# untitled.net
KiCad netlist of a schematic drawn in EAGLE
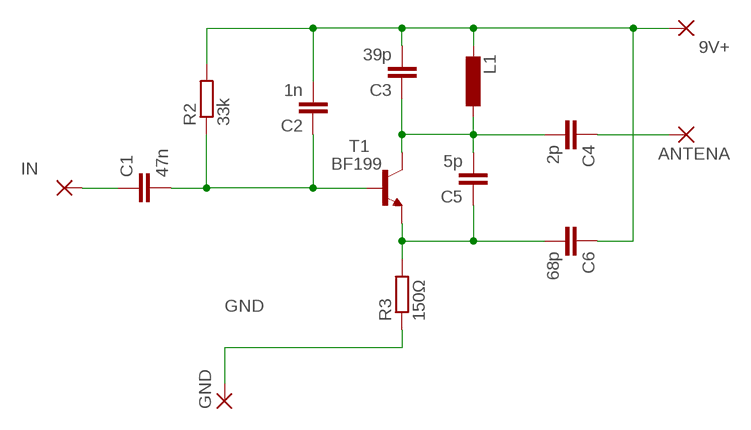
[diagram p0: schematic, sheet 1]

(export (version "E")
  (design (tool "Eeschema 10.0.6"))
  (components
    (comp (ref "9V+")
      (value "3,81/1,4")
      (footprint "eagle-import:3,81_1,4")
      (libsource (lib "eagle-import") (part "3,81/1,4"))
    )
    (comp (ref "ANTENA")
      (value "3,81/1,4")
      (footprint "eagle-import:3,81_1,4")
      (libsource (lib "eagle-import") (part "3,81/1,4"))
    )
    (comp (ref "C1")
      (value "47n")
      (footprint "eagle-import:C025-025X050")
      (libsource (lib "eagle-import") (part "C-EU025-025X050"))
    )
    (comp (ref "C2")
      (value "1n")
      (footprint "eagle-import:C025-025X050")
      (libsource (lib "eagle-import") (part "C-EU025-025X050"))
    )
    (comp (ref "C3")
      (value "39p")
      (footprint "eagle-import:C025-025X050")
      (libsource (lib "eagle-import") (part "C-EU025-025X050"))
    )
    (comp (ref "C4")
      (value "2p")
      (footprint "eagle-import:C025-025X050")
      (libsource (lib "eagle-import") (part "C-EU025-025X050"))
    )
    (comp (ref "C5")
      (value "5p")
      (footprint "eagle-import:C025-025X050")
      (libsource (lib "eagle-import") (part "C-EU025-025X050"))
    )
    (comp (ref "C6")
      (value "68p")
      (footprint "eagle-import:C025-025X050")
      (libsource (lib "eagle-import") (part "C-EU025-025X050"))
    )
    (comp (ref "GND")
      (value "3,81/1,4")
      (footprint "eagle-import:3,81_1,4")
      (libsource (lib "eagle-import") (part "3,81/1,4"))
    )
    (comp (ref "IN")
      (value "3,81/1,4")
      (footprint "eagle-import:3,81_1,4")
      (libsource (lib "eagle-import") (part "3,81/1,4"))
    )
    (comp (ref "L1")
      (value "L-EU0207/7")
      (footprint "eagle-import:0207_7")
      (libsource (lib "eagle-import") (part "L-EU0207/7"))
    )
    (comp (ref "R2")
      (value "33k")
      (footprint "eagle-import:0207_10")
      (libsource (lib "eagle-import") (part "R-EU_0207/10"))
    )
    (comp (ref "R3")
      (value "150Ω")
      (footprint "eagle-import:0207_10")
      (libsource (lib "eagle-import") (part "R-EU_0207/10"))
    )
    (comp (ref "T1")
      (value "BF199")
      (footprint "eagle-import:TO92")
      (libsource (lib "eagle-import") (part "BF199"))
    )
  )
  (nets
    (net (code "1") (name "/GND") (class "Default")
      (node (ref "GND") (pin "1") (pinfunction "P_1") (pintype "passive"))
      (node (ref "R3") (pin "1") (pinfunction "1_1") (pintype "passive"))
    )
    (net (code "2") (name "Net-(9V+-P)") (class "Default")
      (node (ref "9V+") (pin "1") (pinfunction "P_1") (pintype "passive"))
      (node (ref "C2") (pin "2") (pinfunction "2_2") (pintype "passive"))
      (node (ref "C3") (pin "2") (pinfunction "2_2") (pintype "passive"))
      (node (ref "C6") (pin "1") (pinfunction "1_1") (pintype "passive"))
      (node (ref "L1") (pin "2") (pinfunction "2_2") (pintype "passive"))
      (node (ref "R2") (pin "2") (pinfunction "2_2") (pintype "passive"))
    )
    (net (code "3") (name "Net-(ANTENA-P)") (class "Default")
      (node (ref "ANTENA") (pin "1") (pinfunction "P_1") (pintype "passive"))
      (node (ref "C4") (pin "1") (pinfunction "1_1") (pintype "passive"))
    )
    (net (code "4") (name "Net-(IN-P)") (class "Default")
      (node (ref "C1") (pin "1") (pinfunction "1_1") (pintype "passive"))
      (node (ref "IN") (pin "1") (pinfunction "P_1") (pintype "passive"))
    )
    (net (code "5") (name "Net-(T1-B)") (class "Default")
      (node (ref "C1") (pin "2") (pinfunction "2_2") (pintype "passive"))
      (node (ref "C2") (pin "1") (pinfunction "1_1") (pintype "passive"))
      (node (ref "R2") (pin "1") (pinfunction "1_1") (pintype "passive"))
      (node (ref "T1") (pin "1") (pinfunction "B_1") (pintype "passive"))
    )
    (net (code "6") (name "Net-(T1-C)") (class "Default")
      (node (ref "C3") (pin "1") (pinfunction "1_1") (pintype "passive"))
      (node (ref "C4") (pin "2") (pinfunction "2_2") (pintype "passive"))
      (node (ref "C5") (pin "2") (pinfunction "2_2") (pintype "passive"))
      (node (ref "L1") (pin "1") (pinfunction "1_1") (pintype "passive"))
      (node (ref "T1") (pin "3") (pinfunction "C_3") (pintype "passive"))
    )
    (net (code "7") (name "Net-(T1-E)") (class "Default")
      (node (ref "C5") (pin "1") (pinfunction "1_1") (pintype "passive"))
      (node (ref "C6") (pin "2") (pinfunction "2_2") (pintype "passive"))
      (node (ref "R3") (pin "2") (pinfunction "2_2") (pintype "passive"))
      (node (ref "T1") (pin "2") (pinfunction "E_2") (pintype "passive"))
    )
  )
)
